# Charger.net
KiCad netlist of a schematic drawn in EasyEDA Pro
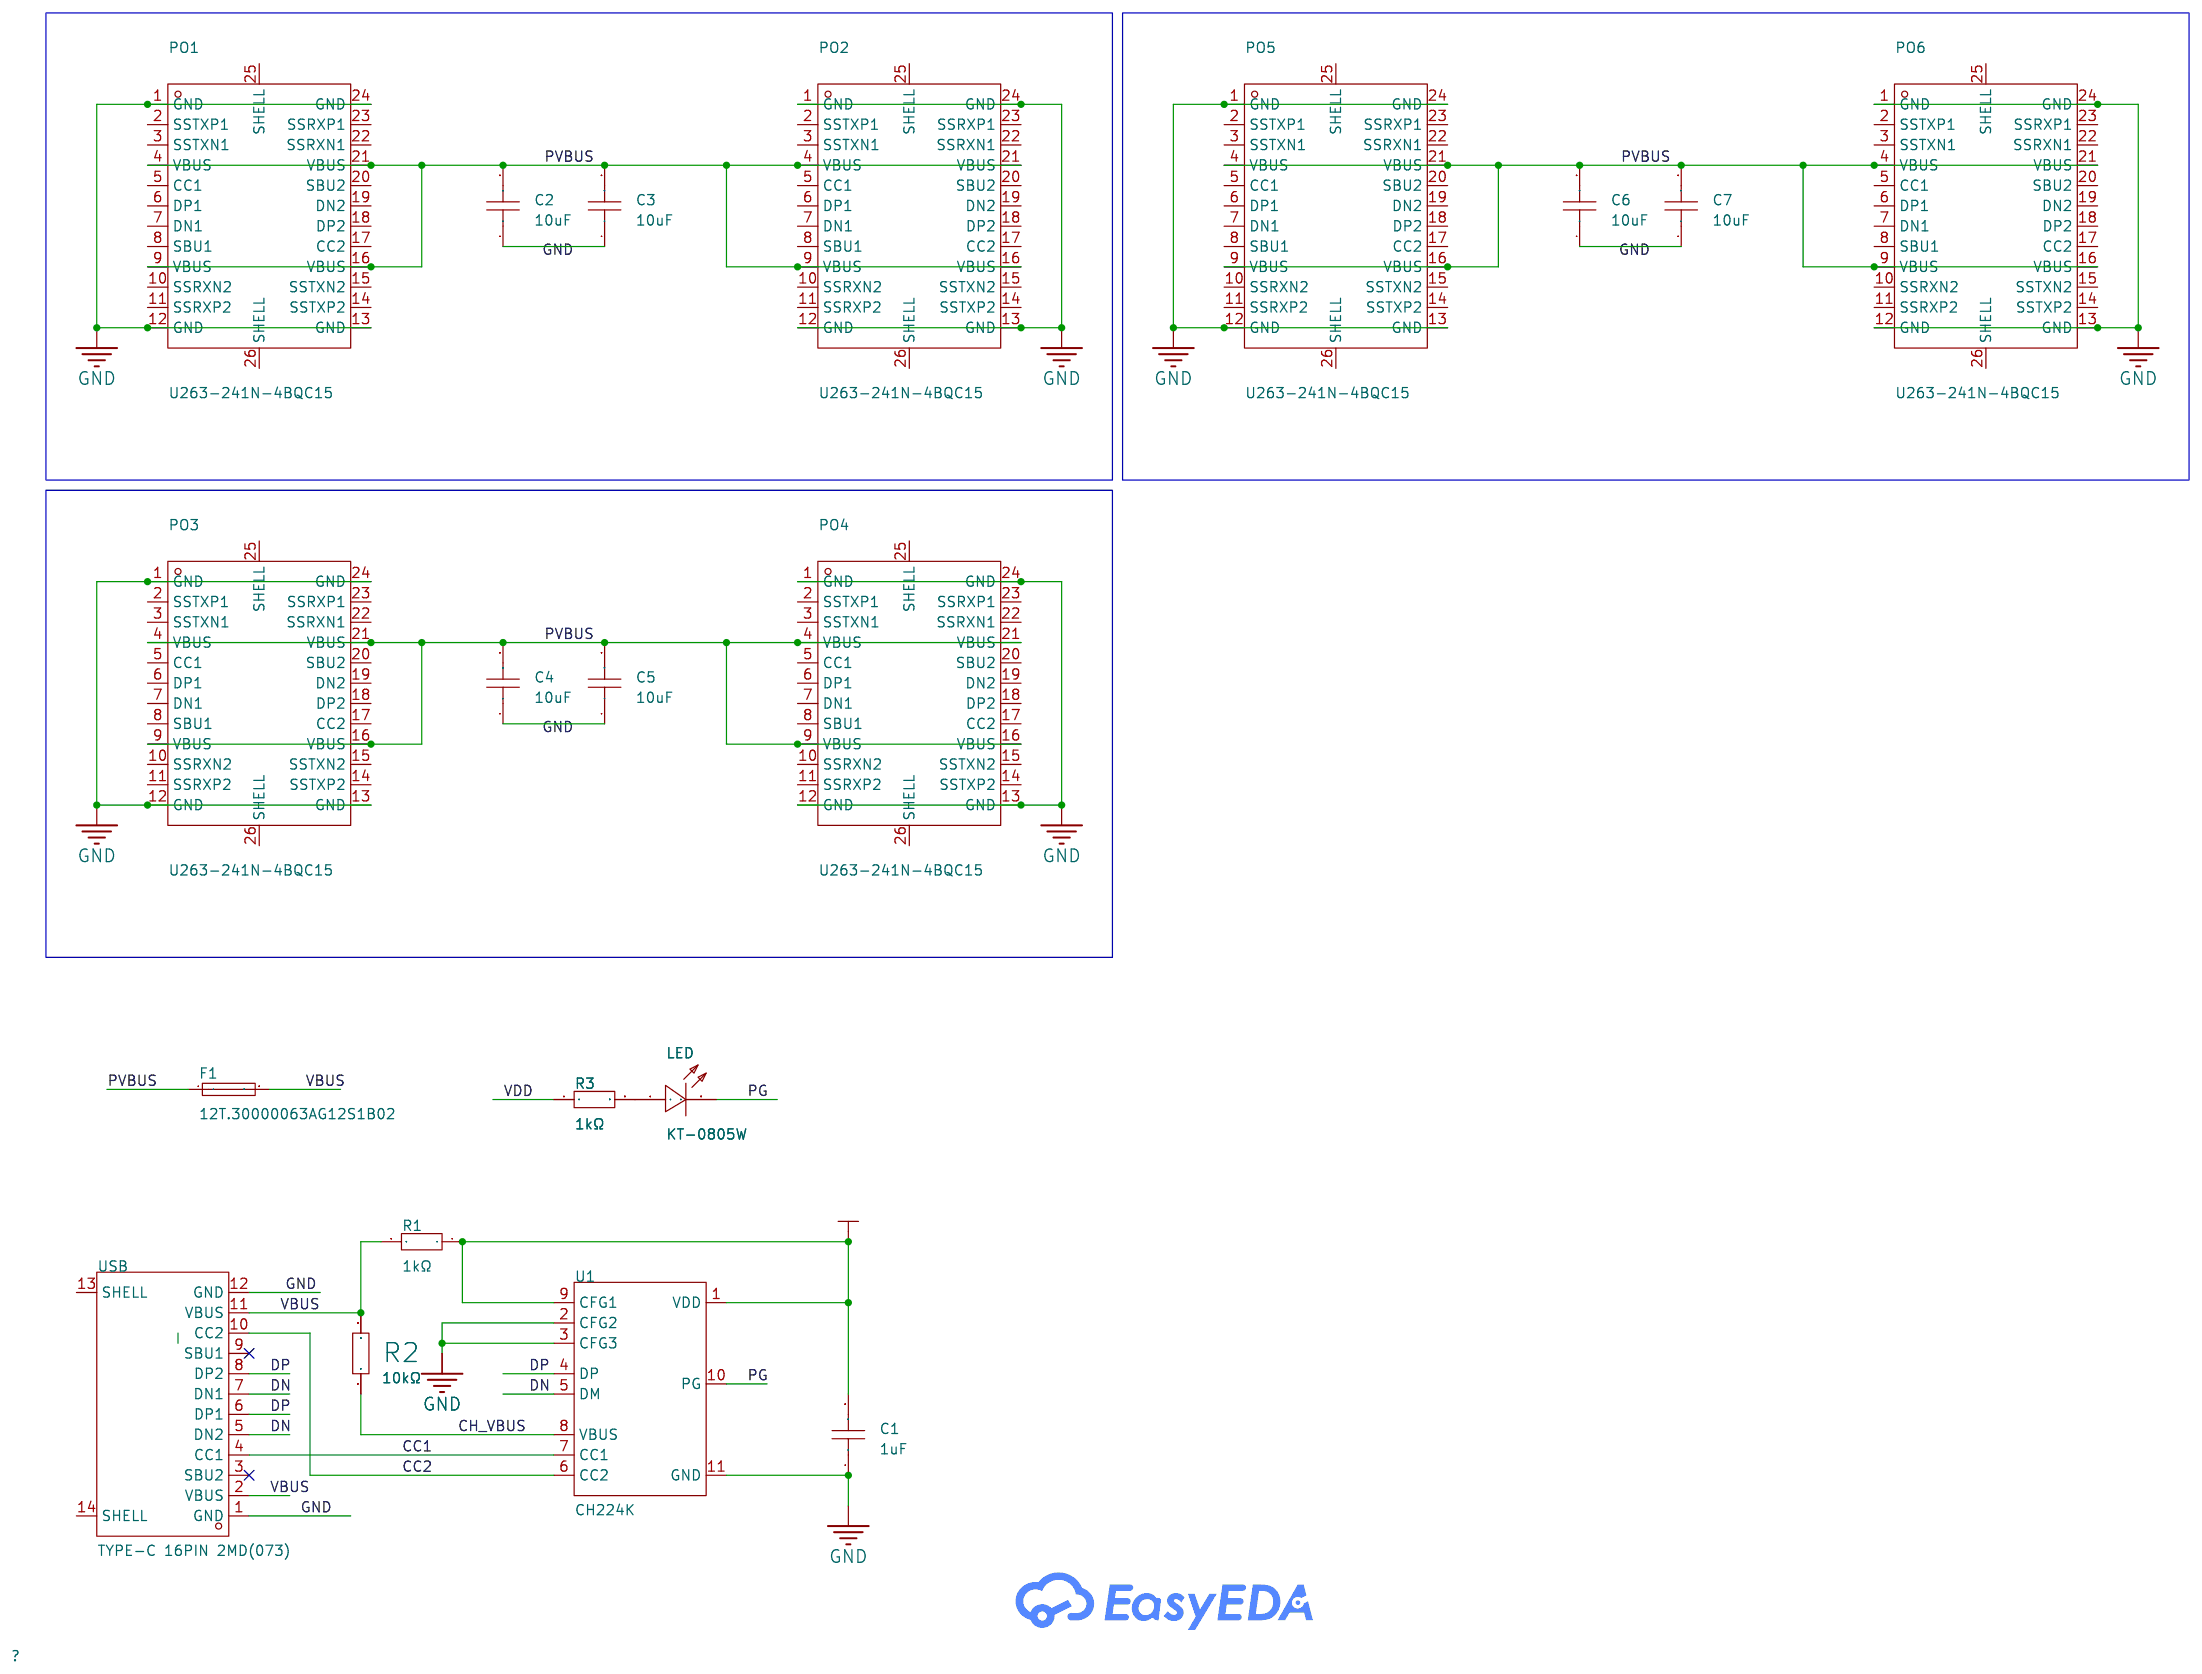
[diagram p0: schematic sheet]

(export (version "E")
  (design (tool "Eeschema 10.0.6"))
  (components
    (comp (ref "C1")
      (value "1uF")
      (footprint "easyedapro:C0603")
      (fields
        (field (name "Manufacturer Part") "CL10A105KB8NNNC")
        (field (name "Manufacturer") "SAMSUNG(三星)")
      )
      (libsource (lib "easyedapro") (part "CL10A105KB8NNNC"))
    )
    (comp (ref "C2")
      (value "10uF")
      (footprint "easyedapro:C0805")
      (fields
        (field (name "Manufacturer Part") "CL21A106KAYNNNE")
        (field (name "Manufacturer") "SAMSUNG(三星)")
      )
      (libsource (lib "easyedapro") (part "CL21A106KAYNNNE"))
    )
    (comp (ref "C3")
      (value "10uF")
      (footprint "easyedapro:C0805")
      (fields
        (field (name "Manufacturer Part") "CL21A106KAYNNNE")
        (field (name "Manufacturer") "SAMSUNG(三星)")
      )
      (libsource (lib "easyedapro") (part "CL21A106KAYNNNE"))
    )
    (comp (ref "C4")
      (value "10uF")
      (footprint "easyedapro:C0805")
      (fields
        (field (name "Manufacturer Part") "CL21A106KAYNNNE")
        (field (name "Manufacturer") "SAMSUNG(三星)")
      )
      (libsource (lib "easyedapro") (part "CL21A106KAYNNNE"))
    )
    (comp (ref "C5")
      (value "10uF")
      (footprint "easyedapro:C0805")
      (fields
        (field (name "Manufacturer Part") "CL21A106KAYNNNE")
        (field (name "Manufacturer") "SAMSUNG(三星)")
      )
      (libsource (lib "easyedapro") (part "CL21A106KAYNNNE"))
    )
    (comp (ref "C6")
      (value "10uF")
      (footprint "easyedapro:C0805")
      (fields
        (field (name "Manufacturer Part") "CL21A106KAYNNNE")
        (field (name "Manufacturer") "SAMSUNG(三星)")
      )
      (libsource (lib "easyedapro") (part "CL21A106KAYNNNE"))
    )
    (comp (ref "C7")
      (value "10uF")
      (footprint "easyedapro:C0805")
      (fields
        (field (name "Manufacturer Part") "CL21A106KAYNNNE")
        (field (name "Manufacturer") "SAMSUNG(三星)")
      )
      (libsource (lib "easyedapro") (part "CL21A106KAYNNNE"))
    )
    (comp (ref "F1")
      (value "12T.30000063AG12S1B02")
      (footprint "easyedapro:F1206")
      (fields (field (name "Manufacturer") "xcfuse(旭程)"))
      (libsource (lib "easyedapro") (part "3A 63V"))
    )
    (comp (ref "LED")
      (value "KT-0805W")
      (footprint "easyedapro:LED0805-R-RD")
      (fields (field (name "Manufacturer") "KENTO"))
      (libsource (lib "easyedapro") (part "whiteLEDSMD"))
    )
    (comp (ref "PO1")
      (value "U263-241N-4BQC15")
      (footprint "easyedapro:USB-C-SMD_U263-241N-4BQC15")
      (fields (field (name "Manufacturer") "XKB Connection(中国星坤)"))
      (libsource (lib "easyedapro") (part "U263-241N-4BQC15"))
    )
    (comp (ref "PO2")
      (value "U263-241N-4BQC15")
      (footprint "easyedapro:USB-C-SMD_U263-241N-4BQC15")
      (fields (field (name "Manufacturer") "XKB Connection(中国星坤)"))
      (libsource (lib "easyedapro") (part "U263-241N-4BQC15"))
    )
    (comp (ref "PO3")
      (value "U263-241N-4BQC15")
      (footprint "easyedapro:USB-C-SMD_U263-241N-4BQC15")
      (fields (field (name "Manufacturer") "XKB Connection(中国星坤)"))
      (libsource (lib "easyedapro") (part "U263-241N-4BQC15"))
    )
    (comp (ref "PO4")
      (value "U263-241N-4BQC15")
      (footprint "easyedapro:USB-C-SMD_U263-241N-4BQC15")
      (fields (field (name "Manufacturer") "XKB Connection(中国星坤)"))
      (libsource (lib "easyedapro") (part "U263-241N-4BQC15"))
    )
    (comp (ref "PO5")
      (value "U263-241N-4BQC15")
      (footprint "easyedapro:USB-C-SMD_U263-241N-4BQC15")
      (fields (field (name "Manufacturer") "XKB Connection(中国星坤)"))
      (libsource (lib "easyedapro") (part "U263-241N-4BQC15"))
    )
    (comp (ref "PO6")
      (value "U263-241N-4BQC15")
      (footprint "easyedapro:USB-C-SMD_U263-241N-4BQC15")
      (fields (field (name "Manufacturer") "XKB Connection(中国星坤)"))
      (libsource (lib "easyedapro") (part "U263-241N-4BQC15"))
    )
    (comp (ref "R1")
      (value "1kΩ")
      (footprint "easyedapro:R0603")
      (fields
        (field (name "Manufacturer Part") "0603WAF1001T5E")
        (field (name "Manufacturer") "UNI-ROYAL(厚声)")
      )
      (libsource (lib "easyedapro") (part "0603WAF1001T5E"))
    )
    (comp (ref "R2")
      (value "10kΩ")
      (footprint "easyedapro:R0603")
      (fields
        (field (name "Manufacturer Part") "0603WAF1002T5E")
        (field (name "Manufacturer") "UNI-ROYAL(厚声)")
      )
      (libsource (lib "easyedapro") (part "0603WAF1002T5E"))
    )
    (comp (ref "R3")
      (value "1kΩ")
      (footprint "easyedapro:R0603")
      (fields
        (field (name "Manufacturer Part") "0603WAF1001T5E")
        (field (name "Manufacturer") "UNI-ROYAL(厚声)")
      )
      (libsource (lib "easyedapro") (part "0603WAF1001T5E"))
    )
    (comp (ref "U1")
      (value "CH224K")
      (footprint "easyedapro:ESSOP-10_L4.9-W3.9-P1.0-LS6.0-TL-EP")
      (fields (field (name "Manufacturer") "WCH(南京沁恒)"))
      (libsource (lib "easyedapro") (part "CH224K"))
    )
    (comp (ref "USB")
      (value "TYPE-C 16PIN 2MD(073)")
      (footprint "easyedapro:USB-C-SMD_TYPE-C-6PIN-2MD-073")
      (fields (field (name "Manufacturer") "SHOU HAN(首韩)"))
      (libsource (lib "easyedapro") (part "TYPE-C 16PIN 2MD(073)"))
    )
  )
  (nets
    (net (code "1") (name "/CC1") (class "Default")
      (node (ref "U1") (pin "7") (pinfunction "CC1_7") (pintype "unspecified"))
      (node (ref "USB") (pin "4") (pinfunction "CC1_4") (pintype "unspecified"))
    )
    (net (code "2") (name "/CC2") (class "Default")
      (node (ref "U1") (pin "6") (pinfunction "CC2_6") (pintype "unspecified"))
      (node (ref "USB") (pin "10") (pinfunction "CC2_10") (pintype "unspecified"))
    )
    (net (code "3") (name "/CH_VBUS") (class "Default")
      (node (ref "R2") (pin "1") (pinfunction "1_1") (pintype "input"))
      (node (ref "U1") (pin "8") (pinfunction "VBUS_8") (pintype "unspecified"))
    )
    (net (code "4") (name "/DN") (class "Default")
      (node (ref "U1") (pin "5") (pinfunction "DM_5") (pintype "unspecified"))
      (node (ref "USB") (pin "5") (pinfunction "DN2_5") (pintype "unspecified"))
      (node (ref "USB") (pin "7") (pinfunction "DN1_7") (pintype "unspecified"))
    )
    (net (code "5") (name "/DP") (class "Default")
      (node (ref "U1") (pin "4") (pinfunction "DP_4") (pintype "unspecified"))
      (node (ref "USB") (pin "6") (pinfunction "DP1_6") (pintype "unspecified"))
      (node (ref "USB") (pin "8") (pinfunction "DP2_8") (pintype "unspecified"))
    )
    (net (code "6") (name "/PG") (class "Default")
      (node (ref "LED") (pin "2") (pinfunction "K_2") (pintype "unspecified"))
      (node (ref "U1") (pin "10") (pinfunction "PG_10") (pintype "unspecified"))
    )
    (net (code "7") (name "/PVBUS") (class "Default")
      (node (ref "C2") (pin "2") (pinfunction "2_2") (pintype "unspecified"))
      (node (ref "C3") (pin "2") (pinfunction "2_2") (pintype "unspecified"))
      (node (ref "C4") (pin "2") (pinfunction "2_2") (pintype "unspecified"))
      (node (ref "C5") (pin "2") (pinfunction "2_2") (pintype "unspecified"))
      (node (ref "C6") (pin "2") (pinfunction "2_2") (pintype "unspecified"))
      (node (ref "C7") (pin "2") (pinfunction "2_2") (pintype "unspecified"))
      (node (ref "F1") (pin "1") (pinfunction "1_1") (pintype "unspecified"))
      (node (ref "PO1") (pin "16") (pinfunction "VBUS_16") (pintype "unspecified"))
      (node (ref "PO1") (pin "21") (pinfunction "VBUS_21") (pintype "unspecified"))
      (node (ref "PO1") (pin "4") (pinfunction "VBUS_4") (pintype "unspecified"))
      (node (ref "PO1") (pin "9") (pinfunction "VBUS_9") (pintype "unspecified"))
      (node (ref "PO2") (pin "16") (pinfunction "VBUS_16") (pintype "unspecified"))
      (node (ref "PO2") (pin "21") (pinfunction "VBUS_21") (pintype "unspecified"))
      (node (ref "PO2") (pin "4") (pinfunction "VBUS_4") (pintype "unspecified"))
      (node (ref "PO2") (pin "9") (pinfunction "VBUS_9") (pintype "unspecified"))
      (node (ref "PO3") (pin "16") (pinfunction "VBUS_16") (pintype "unspecified"))
      (node (ref "PO3") (pin "21") (pinfunction "VBUS_21") (pintype "unspecified"))
      (node (ref "PO3") (pin "4") (pinfunction "VBUS_4") (pintype "unspecified"))
      (node (ref "PO3") (pin "9") (pinfunction "VBUS_9") (pintype "unspecified"))
      (node (ref "PO4") (pin "16") (pinfunction "VBUS_16") (pintype "unspecified"))
      (node (ref "PO4") (pin "21") (pinfunction "VBUS_21") (pintype "unspecified"))
      (node (ref "PO4") (pin "4") (pinfunction "VBUS_4") (pintype "unspecified"))
      (node (ref "PO4") (pin "9") (pinfunction "VBUS_9") (pintype "unspecified"))
      (node (ref "PO5") (pin "16") (pinfunction "VBUS_16") (pintype "unspecified"))
      (node (ref "PO5") (pin "21") (pinfunction "VBUS_21") (pintype "unspecified"))
      (node (ref "PO5") (pin "4") (pinfunction "VBUS_4") (pintype "unspecified"))
      (node (ref "PO5") (pin "9") (pinfunction "VBUS_9") (pintype "unspecified"))
      (node (ref "PO6") (pin "16") (pinfunction "VBUS_16") (pintype "unspecified"))
      (node (ref "PO6") (pin "21") (pinfunction "VBUS_21") (pintype "unspecified"))
      (node (ref "PO6") (pin "4") (pinfunction "VBUS_4") (pintype "unspecified"))
      (node (ref "PO6") (pin "9") (pinfunction "VBUS_9") (pintype "unspecified"))
    )
    (net (code "8") (name "/VBUS") (class "Default")
      (node (ref "F1") (pin "2") (pinfunction "2_2") (pintype "unspecified"))
      (node (ref "R1") (pin "2") (pinfunction "2_2") (pintype "input"))
      (node (ref "R2") (pin "2") (pinfunction "2_2") (pintype "input"))
      (node (ref "USB") (pin "11") (pinfunction "VBUS_11") (pintype "unspecified"))
      (node (ref "USB") (pin "2") (pinfunction "VBUS_2") (pintype "unspecified"))
    )
    (net (code "9") (name "GND") (class "Default")
      (node (ref "C1") (pin "1") (pinfunction "1_1") (pintype "unspecified"))
      (node (ref "C2") (pin "1") (pinfunction "1_1") (pintype "unspecified"))
      (node (ref "C3") (pin "1") (pinfunction "1_1") (pintype "unspecified"))
      (node (ref "C4") (pin "1") (pinfunction "1_1") (pintype "unspecified"))
      (node (ref "C5") (pin "1") (pinfunction "1_1") (pintype "unspecified"))
      (node (ref "C6") (pin "1") (pinfunction "1_1") (pintype "unspecified"))
      (node (ref "C7") (pin "1") (pinfunction "1_1") (pintype "unspecified"))
      (node (ref "PO1") (pin "1") (pinfunction "GND_1") (pintype "unspecified"))
      (node (ref "PO1") (pin "12") (pinfunction "GND_12") (pintype "unspecified"))
      (node (ref "PO1") (pin "13") (pinfunction "GND_13") (pintype "unspecified"))
      (node (ref "PO1") (pin "24") (pinfunction "GND_24") (pintype "unspecified"))
      (node (ref "PO2") (pin "1") (pinfunction "GND_1") (pintype "unspecified"))
      (node (ref "PO2") (pin "12") (pinfunction "GND_12") (pintype "unspecified"))
      (node (ref "PO2") (pin "13") (pinfunction "GND_13") (pintype "unspecified"))
      (node (ref "PO2") (pin "24") (pinfunction "GND_24") (pintype "unspecified"))
      (node (ref "PO3") (pin "1") (pinfunction "GND_1") (pintype "unspecified"))
      (node (ref "PO3") (pin "12") (pinfunction "GND_12") (pintype "unspecified"))
      (node (ref "PO3") (pin "13") (pinfunction "GND_13") (pintype "unspecified"))
      (node (ref "PO3") (pin "24") (pinfunction "GND_24") (pintype "unspecified"))
      (node (ref "PO4") (pin "1") (pinfunction "GND_1") (pintype "unspecified"))
      (node (ref "PO4") (pin "12") (pinfunction "GND_12") (pintype "unspecified"))
      (node (ref "PO4") (pin "13") (pinfunction "GND_13") (pintype "unspecified"))
      (node (ref "PO4") (pin "24") (pinfunction "GND_24") (pintype "unspecified"))
      (node (ref "PO5") (pin "1") (pinfunction "GND_1") (pintype "unspecified"))
      (node (ref "PO5") (pin "12") (pinfunction "GND_12") (pintype "unspecified"))
      (node (ref "PO5") (pin "13") (pinfunction "GND_13") (pintype "unspecified"))
      (node (ref "PO5") (pin "24") (pinfunction "GND_24") (pintype "unspecified"))
      (node (ref "PO6") (pin "1") (pinfunction "GND_1") (pintype "unspecified"))
      (node (ref "PO6") (pin "12") (pinfunction "GND_12") (pintype "unspecified"))
      (node (ref "PO6") (pin "13") (pinfunction "GND_13") (pintype "unspecified"))
      (node (ref "PO6") (pin "24") (pinfunction "GND_24") (pintype "unspecified"))
      (node (ref "U1") (pin "11") (pinfunction "GND_11") (pintype "unspecified"))
      (node (ref "U1") (pin "2") (pinfunction "CFG2_2") (pintype "unspecified"))
      (node (ref "U1") (pin "3") (pinfunction "CFG3_3") (pintype "unspecified"))
      (node (ref "USB") (pin "1") (pinfunction "GND_1") (pintype "unspecified"))
      (node (ref "USB") (pin "12") (pinfunction "GND_12") (pintype "unspecified"))
    )
    (net (code "10") (name "Net-(LED-A)") (class "Default")
      (node (ref "LED") (pin "1") (pinfunction "A_1") (pintype "unspecified"))
      (node (ref "R3") (pin "2") (pinfunction "2_2") (pintype "input"))
    )
    (net (code "11") (name "VDD") (class "Default")
      (node (ref "C1") (pin "2") (pinfunction "2_2") (pintype "unspecified"))
      (node (ref "R1") (pin "1") (pinfunction "1_1") (pintype "input"))
      (node (ref "R3") (pin "1") (pinfunction "1_1") (pintype "input"))
      (node (ref "U1") (pin "1") (pinfunction "VDD_1") (pintype "unspecified"))
      (node (ref "U1") (pin "9") (pinfunction "CFG1_9") (pintype "unspecified"))
    )
    (net (code "12") (name "unconnected-(PO1-CC1-Pad5)") (class "Default")
      (node (ref "PO1") (pin "5") (pinfunction "CC1_5") (pintype "unspecified"))
    )
    (net (code "13") (name "unconnected-(PO1-CC2-Pad17)") (class "Default")
      (node (ref "PO1") (pin "17") (pinfunction "CC2_17") (pintype "unspecified"))
    )
    (net (code "14") (name "unconnected-(PO1-DN1-Pad7)") (class "Default")
      (node (ref "PO1") (pin "7") (pinfunction "DN1_7") (pintype "unspecified"))
    )
    (net (code "15") (name "unconnected-(PO1-DN2-Pad19)") (class "Default")
      (node (ref "PO1") (pin "19") (pinfunction "DN2_19") (pintype "unspecified"))
    )
    (net (code "16") (name "unconnected-(PO1-DP1-Pad6)") (class "Default")
      (node (ref "PO1") (pin "6") (pinfunction "DP1_6") (pintype "unspecified"))
    )
    (net (code "17") (name "unconnected-(PO1-DP2-Pad18)") (class "Default")
      (node (ref "PO1") (pin "18") (pinfunction "DP2_18") (pintype "unspecified"))
    )
    (net (code "18") (name "unconnected-(PO1-SBU1-Pad8)") (class "Default")
      (node (ref "PO1") (pin "8") (pinfunction "SBU1_8") (pintype "unspecified"))
    )
    (net (code "19") (name "unconnected-(PO1-SBU2-Pad20)") (class "Default")
      (node (ref "PO1") (pin "20") (pinfunction "SBU2_20") (pintype "unspecified"))
    )
    (net (code "20") (name "unconnected-(PO1-SHELL-Pad25)") (class "Default")
      (node (ref "PO1") (pin "25") (pinfunction "SHELL_25") (pintype "unspecified"))
    )
    (net (code "21") (name "unconnected-(PO1-SHELL-Pad26)") (class "Default")
      (node (ref "PO1") (pin "26") (pinfunction "SHELL_26") (pintype "unspecified"))
    )
    (net (code "22") (name "unconnected-(PO1-SSRXN1-Pad22)") (class "Default")
      (node (ref "PO1") (pin "22") (pinfunction "SSRXN1_22") (pintype "unspecified"))
    )
    (net (code "23") (name "unconnected-(PO1-SSRXN2-Pad10)") (class "Default")
      (node (ref "PO1") (pin "10") (pinfunction "SSRXN2_10") (pintype "unspecified"))
    )
    (net (code "24") (name "unconnected-(PO1-SSRXP1-Pad23)") (class "Default")
      (node (ref "PO1") (pin "23") (pinfunction "SSRXP1_23") (pintype "unspecified"))
    )
    (net (code "25") (name "unconnected-(PO1-SSRXP2-Pad11)") (class "Default")
      (node (ref "PO1") (pin "11") (pinfunction "SSRXP2_11") (pintype "unspecified"))
    )
    (net (code "26") (name "unconnected-(PO1-SSTXN1-Pad3)") (class "Default")
      (node (ref "PO1") (pin "3") (pinfunction "SSTXN1_3") (pintype "unspecified"))
    )
    (net (code "27") (name "unconnected-(PO1-SSTXN2-Pad15)") (class "Default")
      (node (ref "PO1") (pin "15") (pinfunction "SSTXN2_15") (pintype "unspecified"))
    )
    (net (code "28") (name "unconnected-(PO1-SSTXP1-Pad2)") (class "Default")
      (node (ref "PO1") (pin "2") (pinfunction "SSTXP1_2") (pintype "unspecified"))
    )
    (net (code "29") (name "unconnected-(PO1-SSTXP2-Pad14)") (class "Default")
      (node (ref "PO1") (pin "14") (pinfunction "SSTXP2_14") (pintype "unspecified"))
    )
    (net (code "30") (name "unconnected-(PO2-CC1-Pad5)") (class "Default")
      (node (ref "PO2") (pin "5") (pinfunction "CC1_5") (pintype "unspecified"))
    )
    (net (code "31") (name "unconnected-(PO2-CC2-Pad17)") (class "Default")
      (node (ref "PO2") (pin "17") (pinfunction "CC2_17") (pintype "unspecified"))
    )
    (net (code "32") (name "unconnected-(PO2-DN1-Pad7)") (class "Default")
      (node (ref "PO2") (pin "7") (pinfunction "DN1_7") (pintype "unspecified"))
    )
    (net (code "33") (name "unconnected-(PO2-DN2-Pad19)") (class "Default")
      (node (ref "PO2") (pin "19") (pinfunction "DN2_19") (pintype "unspecified"))
    )
    (net (code "34") (name "unconnected-(PO2-DP1-Pad6)") (class "Default")
      (node (ref "PO2") (pin "6") (pinfunction "DP1_6") (pintype "unspecified"))
    )
    (net (code "35") (name "unconnected-(PO2-DP2-Pad18)") (class "Default")
      (node (ref "PO2") (pin "18") (pinfunction "DP2_18") (pintype "unspecified"))
    )
    (net (code "36") (name "unconnected-(PO2-SBU1-Pad8)") (class "Default")
      (node (ref "PO2") (pin "8") (pinfunction "SBU1_8") (pintype "unspecified"))
    )
    (net (code "37") (name "unconnected-(PO2-SBU2-Pad20)") (class "Default")
      (node (ref "PO2") (pin "20") (pinfunction "SBU2_20") (pintype "unspecified"))
    )
    (net (code "38") (name "unconnected-(PO2-SHELL-Pad25)") (class "Default")
      (node (ref "PO2") (pin "25") (pinfunction "SHELL_25") (pintype "unspecified"))
    )
    (net (code "39") (name "unconnected-(PO2-SHELL-Pad26)") (class "Default")
      (node (ref "PO2") (pin "26") (pinfunction "SHELL_26") (pintype "unspecified"))
    )
    (net (code "40") (name "unconnected-(PO2-SSRXN1-Pad22)") (class "Default")
      (node (ref "PO2") (pin "22") (pinfunction "SSRXN1_22") (pintype "unspecified"))
    )
    (net (code "41") (name "unconnected-(PO2-SSRXN2-Pad10)") (class "Default")
      (node (ref "PO2") (pin "10") (pinfunction "SSRXN2_10") (pintype "unspecified"))
    )
    (net (code "42") (name "unconnected-(PO2-SSRXP1-Pad23)") (class "Default")
      (node (ref "PO2") (pin "23") (pinfunction "SSRXP1_23") (pintype "unspecified"))
    )
    (net (code "43") (name "unconnected-(PO2-SSRXP2-Pad11)") (class "Default")
      (node (ref "PO2") (pin "11") (pinfunction "SSRXP2_11") (pintype "unspecified"))
    )
    (net (code "44") (name "unconnected-(PO2-SSTXN1-Pad3)") (class "Default")
      (node (ref "PO2") (pin "3") (pinfunction "SSTXN1_3") (pintype "unspecified"))
    )
    (net (code "45") (name "unconnected-(PO2-SSTXN2-Pad15)") (class "Default")
      (node (ref "PO2") (pin "15") (pinfunction "SSTXN2_15") (pintype "unspecified"))
    )
    (net (code "46") (name "unconnected-(PO2-SSTXP1-Pad2)") (class "Default")
      (node (ref "PO2") (pin "2") (pinfunction "SSTXP1_2") (pintype "unspecified"))
    )
    (net (code "47") (name "unconnected-(PO2-SSTXP2-Pad14)") (class "Default")
      (node (ref "PO2") (pin "14") (pinfunction "SSTXP2_14") (pintype "unspecified"))
    )
    (net (code "48") (name "unconnected-(PO3-CC1-Pad5)") (class "Default")
      (node (ref "PO3") (pin "5") (pinfunction "CC1_5") (pintype "unspecified"))
    )
    (net (code "49") (name "unconnected-(PO3-CC2-Pad17)") (class "Default")
      (node (ref "PO3") (pin "17") (pinfunction "CC2_17") (pintype "unspecified"))
    )
    (net (code "50") (name "unconnected-(PO3-DN1-Pad7)") (class "Default")
      (node (ref "PO3") (pin "7") (pinfunction "DN1_7") (pintype "unspecified"))
    )
    (net (code "51") (name "unconnected-(PO3-DN2-Pad19)") (class "Default")
      (node (ref "PO3") (pin "19") (pinfunction "DN2_19") (pintype "unspecified"))
    )
    (net (code "52") (name "unconnected-(PO3-DP1-Pad6)") (class "Default")
      (node (ref "PO3") (pin "6") (pinfunction "DP1_6") (pintype "unspecified"))
    )
    (net (code "53") (name "unconnected-(PO3-DP2-Pad18)") (class "Default")
      (node (ref "PO3") (pin "18") (pinfunction "DP2_18") (pintype "unspecified"))
    )
    (net (code "54") (name "unconnected-(PO3-SBU1-Pad8)") (class "Default")
      (node (ref "PO3") (pin "8") (pinfunction "SBU1_8") (pintype "unspecified"))
    )
    (net (code "55") (name "unconnected-(PO3-SBU2-Pad20)") (class "Default")
      (node (ref "PO3") (pin "20") (pinfunction "SBU2_20") (pintype "unspecified"))
    )
    (net (code "56") (name "unconnected-(PO3-SHELL-Pad25)") (class "Default")
      (node (ref "PO3") (pin "25") (pinfunction "SHELL_25") (pintype "unspecified"))
    )
    (net (code "57") (name "unconnected-(PO3-SHELL-Pad26)") (class "Default")
      (node (ref "PO3") (pin "26") (pinfunction "SHELL_26") (pintype "unspecified"))
    )
    (net (code "58") (name "unconnected-(PO3-SSRXN1-Pad22)") (class "Default")
      (node (ref "PO3") (pin "22") (pinfunction "SSRXN1_22") (pintype "unspecified"))
    )
    (net (code "59") (name "unconnected-(PO3-SSRXN2-Pad10)") (class "Default")
      (node (ref "PO3") (pin "10") (pinfunction "SSRXN2_10") (pintype "unspecified"))
    )
    (net (code "60") (name "unconnected-(PO3-SSRXP1-Pad23)") (class "Default")
      (node (ref "PO3") (pin "23") (pinfunction "SSRXP1_23") (pintype "unspecified"))
    )
    (net (code "61") (name "unconnected-(PO3-SSRXP2-Pad11)") (class "Default")
      (node (ref "PO3") (pin "11") (pinfunction "SSRXP2_11") (pintype "unspecified"))
    )
    (net (code "62") (name "unconnected-(PO3-SSTXN1-Pad3)") (class "Default")
      (node (ref "PO3") (pin "3") (pinfunction "SSTXN1_3") (pintype "unspecified"))
    )
    (net (code "63") (name "unconnected-(PO3-SSTXN2-Pad15)") (class "Default")
      (node (ref "PO3") (pin "15") (pinfunction "SSTXN2_15") (pintype "unspecified"))
    )
    (net (code "64") (name "unconnected-(PO3-SSTXP1-Pad2)") (class "Default")
      (node (ref "PO3") (pin "2") (pinfunction "SSTXP1_2") (pintype "unspecified"))
    )
    (net (code "65") (name "unconnected-(PO3-SSTXP2-Pad14)") (class "Default")
      (node (ref "PO3") (pin "14") (pinfunction "SSTXP2_14") (pintype "unspecified"))
    )
    (net (code "66") (name "unconnected-(PO4-CC1-Pad5)") (class "Default")
      (node (ref "PO4") (pin "5") (pinfunction "CC1_5") (pintype "unspecified"))
    )
    (net (code "67") (name "unconnected-(PO4-CC2-Pad17)") (class "Default")
      (node (ref "PO4") (pin "17") (pinfunction "CC2_17") (pintype "unspecified"))
    )
    (net (code "68") (name "unconnected-(PO4-DN1-Pad7)") (class "Default")
      (node (ref "PO4") (pin "7") (pinfunction "DN1_7") (pintype "unspecified"))
    )
    (net (code "69") (name "unconnected-(PO4-DN2-Pad19)") (class "Default")
      (node (ref "PO4") (pin "19") (pinfunction "DN2_19") (pintype "unspecified"))
    )
    (net (code "70") (name "unconnected-(PO4-DP1-Pad6)") (class "Default")
      (node (ref "PO4") (pin "6") (pinfunction "DP1_6") (pintype "unspecified"))
    )
    (net (code "71") (name "unconnected-(PO4-DP2-Pad18)") (class "Default")
      (node (ref "PO4") (pin "18") (pinfunction "DP2_18") (pintype "unspecified"))
    )
    (net (code "72") (name "unconnected-(PO4-SBU1-Pad8)") (class "Default")
      (node (ref "PO4") (pin "8") (pinfunction "SBU1_8") (pintype "unspecified"))
    )
    (net (code "73") (name "unconnected-(PO4-SBU2-Pad20)") (class "Default")
      (node (ref "PO4") (pin "20") (pinfunction "SBU2_20") (pintype "unspecified"))
    )
    (net (code "74") (name "unconnected-(PO4-SHELL-Pad25)") (class "Default")
      (node (ref "PO4") (pin "25") (pinfunction "SHELL_25") (pintype "unspecified"))
    )
    (net (code "75") (name "unconnected-(PO4-SHELL-Pad26)") (class "Default")
      (node (ref "PO4") (pin "26") (pinfunction "SHELL_26") (pintype "unspecified"))
    )
    (net (code "76") (name "unconnected-(PO4-SSRXN1-Pad22)") (class "Default")
      (node (ref "PO4") (pin "22") (pinfunction "SSRXN1_22") (pintype "unspecified"))
    )
    (net (code "77") (name "unconnected-(PO4-SSRXN2-Pad10)") (class "Default")
      (node (ref "PO4") (pin "10") (pinfunction "SSRXN2_10") (pintype "unspecified"))
    )
    (net (code "78") (name "unconnected-(PO4-SSRXP1-Pad23)") (class "Default")
      (node (ref "PO4") (pin "23") (pinfunction "SSRXP1_23") (pintype "unspecified"))
    )
    (net (code "79") (name "unconnected-(PO4-SSRXP2-Pad11)") (class "Default")
      (node (ref "PO4") (pin "11") (pinfunction "SSRXP2_11") (pintype "unspecified"))
    )
    (net (code "80") (name "unconnected-(PO4-SSTXN1-Pad3)") (class "Default")
      (node (ref "PO4") (pin "3") (pinfunction "SSTXN1_3") (pintype "unspecified"))
    )
    (net (code "81") (name "unconnected-(PO4-SSTXN2-Pad15)") (class "Default")
      (node (ref "PO4") (pin "15") (pinfunction "SSTXN2_15") (pintype "unspecified"))
    )
    (net (code "82") (name "unconnected-(PO4-SSTXP1-Pad2)") (class "Default")
      (node (ref "PO4") (pin "2") (pinfunction "SSTXP1_2") (pintype "unspecified"))
    )
    (net (code "83") (name "unconnected-(PO4-SSTXP2-Pad14)") (class "Default")
      (node (ref "PO4") (pin "14") (pinfunction "SSTXP2_14") (pintype "unspecified"))
    )
    (net (code "84") (name "unconnected-(PO5-CC1-Pad5)") (class "Default")
      (node (ref "PO5") (pin "5") (pinfunction "CC1_5") (pintype "unspecified"))
    )
    (net (code "85") (name "unconnected-(PO5-CC2-Pad17)") (class "Default")
      (node (ref "PO5") (pin "17") (pinfunction "CC2_17") (pintype "unspecified"))
    )
    (net (code "86") (name "unconnected-(PO5-DN1-Pad7)") (class "Default")
      (node (ref "PO5") (pin "7") (pinfunction "DN1_7") (pintype "unspecified"))
    )
    (net (code "87") (name "unconnected-(PO5-DN2-Pad19)") (class "Default")
      (node (ref "PO5") (pin "19") (pinfunction "DN2_19") (pintype "unspecified"))
    )
    (net (code "88") (name "unconnected-(PO5-DP1-Pad6)") (class "Default")
      (node (ref "PO5") (pin "6") (pinfunction "DP1_6") (pintype "unspecified"))
    )
    (net (code "89") (name "unconnected-(PO5-DP2-Pad18)") (class "Default")
      (node (ref "PO5") (pin "18") (pinfunction "DP2_18") (pintype "unspecified"))
    )
    (net (code "90") (name "unconnected-(PO5-SBU1-Pad8)") (class "Default")
      (node (ref "PO5") (pin "8") (pinfunction "SBU1_8") (pintype "unspecified"))
    )
    (net (code "91") (name "unconnected-(PO5-SBU2-Pad20)") (class "Default")
      (node (ref "PO5") (pin "20") (pinfunction "SBU2_20") (pintype "unspecified"))
    )
    (net (code "92") (name "unconnected-(PO5-SHELL-Pad25)") (class "Default")
      (node (ref "PO5") (pin "25") (pinfunction "SHELL_25") (pintype "unspecified"))
    )
    (net (code "93") (name "unconnected-(PO5-SHELL-Pad26)") (class "Default")
      (node (ref "PO5") (pin "26") (pinfunction "SHELL_26") (pintype "unspecified"))
    )
    (net (code "94") (name "unconnected-(PO5-SSRXN1-Pad22)") (class "Default")
      (node (ref "PO5") (pin "22") (pinfunction "SSRXN1_22") (pintype "unspecified"))
    )
    (net (code "95") (name "unconnected-(PO5-SSRXN2-Pad10)") (class "Default")
      (node (ref "PO5") (pin "10") (pinfunction "SSRXN2_10") (pintype "unspecified"))
    )
    (net (code "96") (name "unconnected-(PO5-SSRXP1-Pad23)") (class "Default")
      (node (ref "PO5") (pin "23") (pinfunction "SSRXP1_23") (pintype "unspecified"))
    )
    (net (code "97") (name "unconnected-(PO5-SSRXP2-Pad11)") (class "Default")
      (node (ref "PO5") (pin "11") (pinfunction "SSRXP2_11") (pintype "unspecified"))
    )
    (net (code "98") (name "unconnected-(PO5-SSTXN1-Pad3)") (class "Default")
      (node (ref "PO5") (pin "3") (pinfunction "SSTXN1_3") (pintype "unspecified"))
    )
    (net (code "99") (name "unconnected-(PO5-SSTXN2-Pad15)") (class "Default")
      (node (ref "PO5") (pin "15") (pinfunction "SSTXN2_15") (pintype "unspecified"))
    )
    (net (code "100") (name "unconnected-(PO5-SSTXP1-Pad2)") (class "Default")
      (node (ref "PO5") (pin "2") (pinfunction "SSTXP1_2") (pintype "unspecified"))
    )
    (net (code "101") (name "unconnected-(PO5-SSTXP2-Pad14)") (class "Default")
      (node (ref "PO5") (pin "14") (pinfunction "SSTXP2_14") (pintype "unspecified"))
    )
    (net (code "102") (name "unconnected-(PO6-CC1-Pad5)") (class "Default")
      (node (ref "PO6") (pin "5") (pinfunction "CC1_5") (pintype "unspecified"))
    )
    (net (code "103") (name "unconnected-(PO6-CC2-Pad17)") (class "Default")
      (node (ref "PO6") (pin "17") (pinfunction "CC2_17") (pintype "unspecified"))
    )
    (net (code "104") (name "unconnected-(PO6-DN1-Pad7)") (class "Default")
      (node (ref "PO6") (pin "7") (pinfunction "DN1_7") (pintype "unspecified"))
    )
    (net (code "105") (name "unconnected-(PO6-DN2-Pad19)") (class "Default")
      (node (ref "PO6") (pin "19") (pinfunction "DN2_19") (pintype "unspecified"))
    )
    (net (code "106") (name "unconnected-(PO6-DP1-Pad6)") (class "Default")
      (node (ref "PO6") (pin "6") (pinfunction "DP1_6") (pintype "unspecified"))
    )
    (net (code "107") (name "unconnected-(PO6-DP2-Pad18)") (class "Default")
      (node (ref "PO6") (pin "18") (pinfunction "DP2_18") (pintype "unspecified"))
    )
    (net (code "108") (name "unconnected-(PO6-SBU1-Pad8)") (class "Default")
      (node (ref "PO6") (pin "8") (pinfunction "SBU1_8") (pintype "unspecified"))
    )
    (net (code "109") (name "unconnected-(PO6-SBU2-Pad20)") (class "Default")
      (node (ref "PO6") (pin "20") (pinfunction "SBU2_20") (pintype "unspecified"))
    )
    (net (code "110") (name "unconnected-(PO6-SHELL-Pad25)") (class "Default")
      (node (ref "PO6") (pin "25") (pinfunction "SHELL_25") (pintype "unspecified"))
    )
    (net (code "111") (name "unconnected-(PO6-SHELL-Pad26)") (class "Default")
      (node (ref "PO6") (pin "26") (pinfunction "SHELL_26") (pintype "unspecified"))
    )
    (net (code "112") (name "unconnected-(PO6-SSRXN1-Pad22)") (class "Default")
      (node (ref "PO6") (pin "22") (pinfunction "SSRXN1_22") (pintype "unspecified"))
    )
    (net (code "113") (name "unconnected-(PO6-SSRXN2-Pad10)") (class "Default")
      (node (ref "PO6") (pin "10") (pinfunction "SSRXN2_10") (pintype "unspecified"))
    )
    (net (code "114") (name "unconnected-(PO6-SSRXP1-Pad23)") (class "Default")
      (node (ref "PO6") (pin "23") (pinfunction "SSRXP1_23") (pintype "unspecified"))
    )
    (net (code "115") (name "unconnected-(PO6-SSRXP2-Pad11)") (class "Default")
      (node (ref "PO6") (pin "11") (pinfunction "SSRXP2_11") (pintype "unspecified"))
    )
    (net (code "116") (name "unconnected-(PO6-SSTXN1-Pad3)") (class "Default")
      (node (ref "PO6") (pin "3") (pinfunction "SSTXN1_3") (pintype "unspecified"))
    )
    (net (code "117") (name "unconnected-(PO6-SSTXN2-Pad15)") (class "Default")
      (node (ref "PO6") (pin "15") (pinfunction "SSTXN2_15") (pintype "unspecified"))
    )
    (net (code "118") (name "unconnected-(PO6-SSTXP1-Pad2)") (class "Default")
      (node (ref "PO6") (pin "2") (pinfunction "SSTXP1_2") (pintype "unspecified"))
    )
    (net (code "119") (name "unconnected-(PO6-SSTXP2-Pad14)") (class "Default")
      (node (ref "PO6") (pin "14") (pinfunction "SSTXP2_14") (pintype "unspecified"))
    )
    (net (code "120") (name "unconnected-(USB-SBU1-Pad9)") (class "Default")
      (node (ref "USB") (pin "9") (pinfunction "SBU1_9") (pintype "unspecified+no_connect"))
    )
    (net (code "121") (name "unconnected-(USB-SBU2-Pad3)") (class "Default")
      (node (ref "USB") (pin "3") (pinfunction "SBU2_3") (pintype "unspecified+no_connect"))
    )
    (net (code "122") (name "unconnected-(USB-SHELL-Pad13)") (class "Default")
      (node (ref "USB") (pin "13") (pinfunction "SHELL_13") (pintype "unspecified"))
    )
    (net (code "123") (name "unconnected-(USB-SHELL-Pad14)") (class "Default")
      (node (ref "USB") (pin "14") (pinfunction "SHELL_14") (pintype "unspecified"))
    )
  )
)
